# MCU.net
KiCad netlist of a schematic drawn in Altium Designer
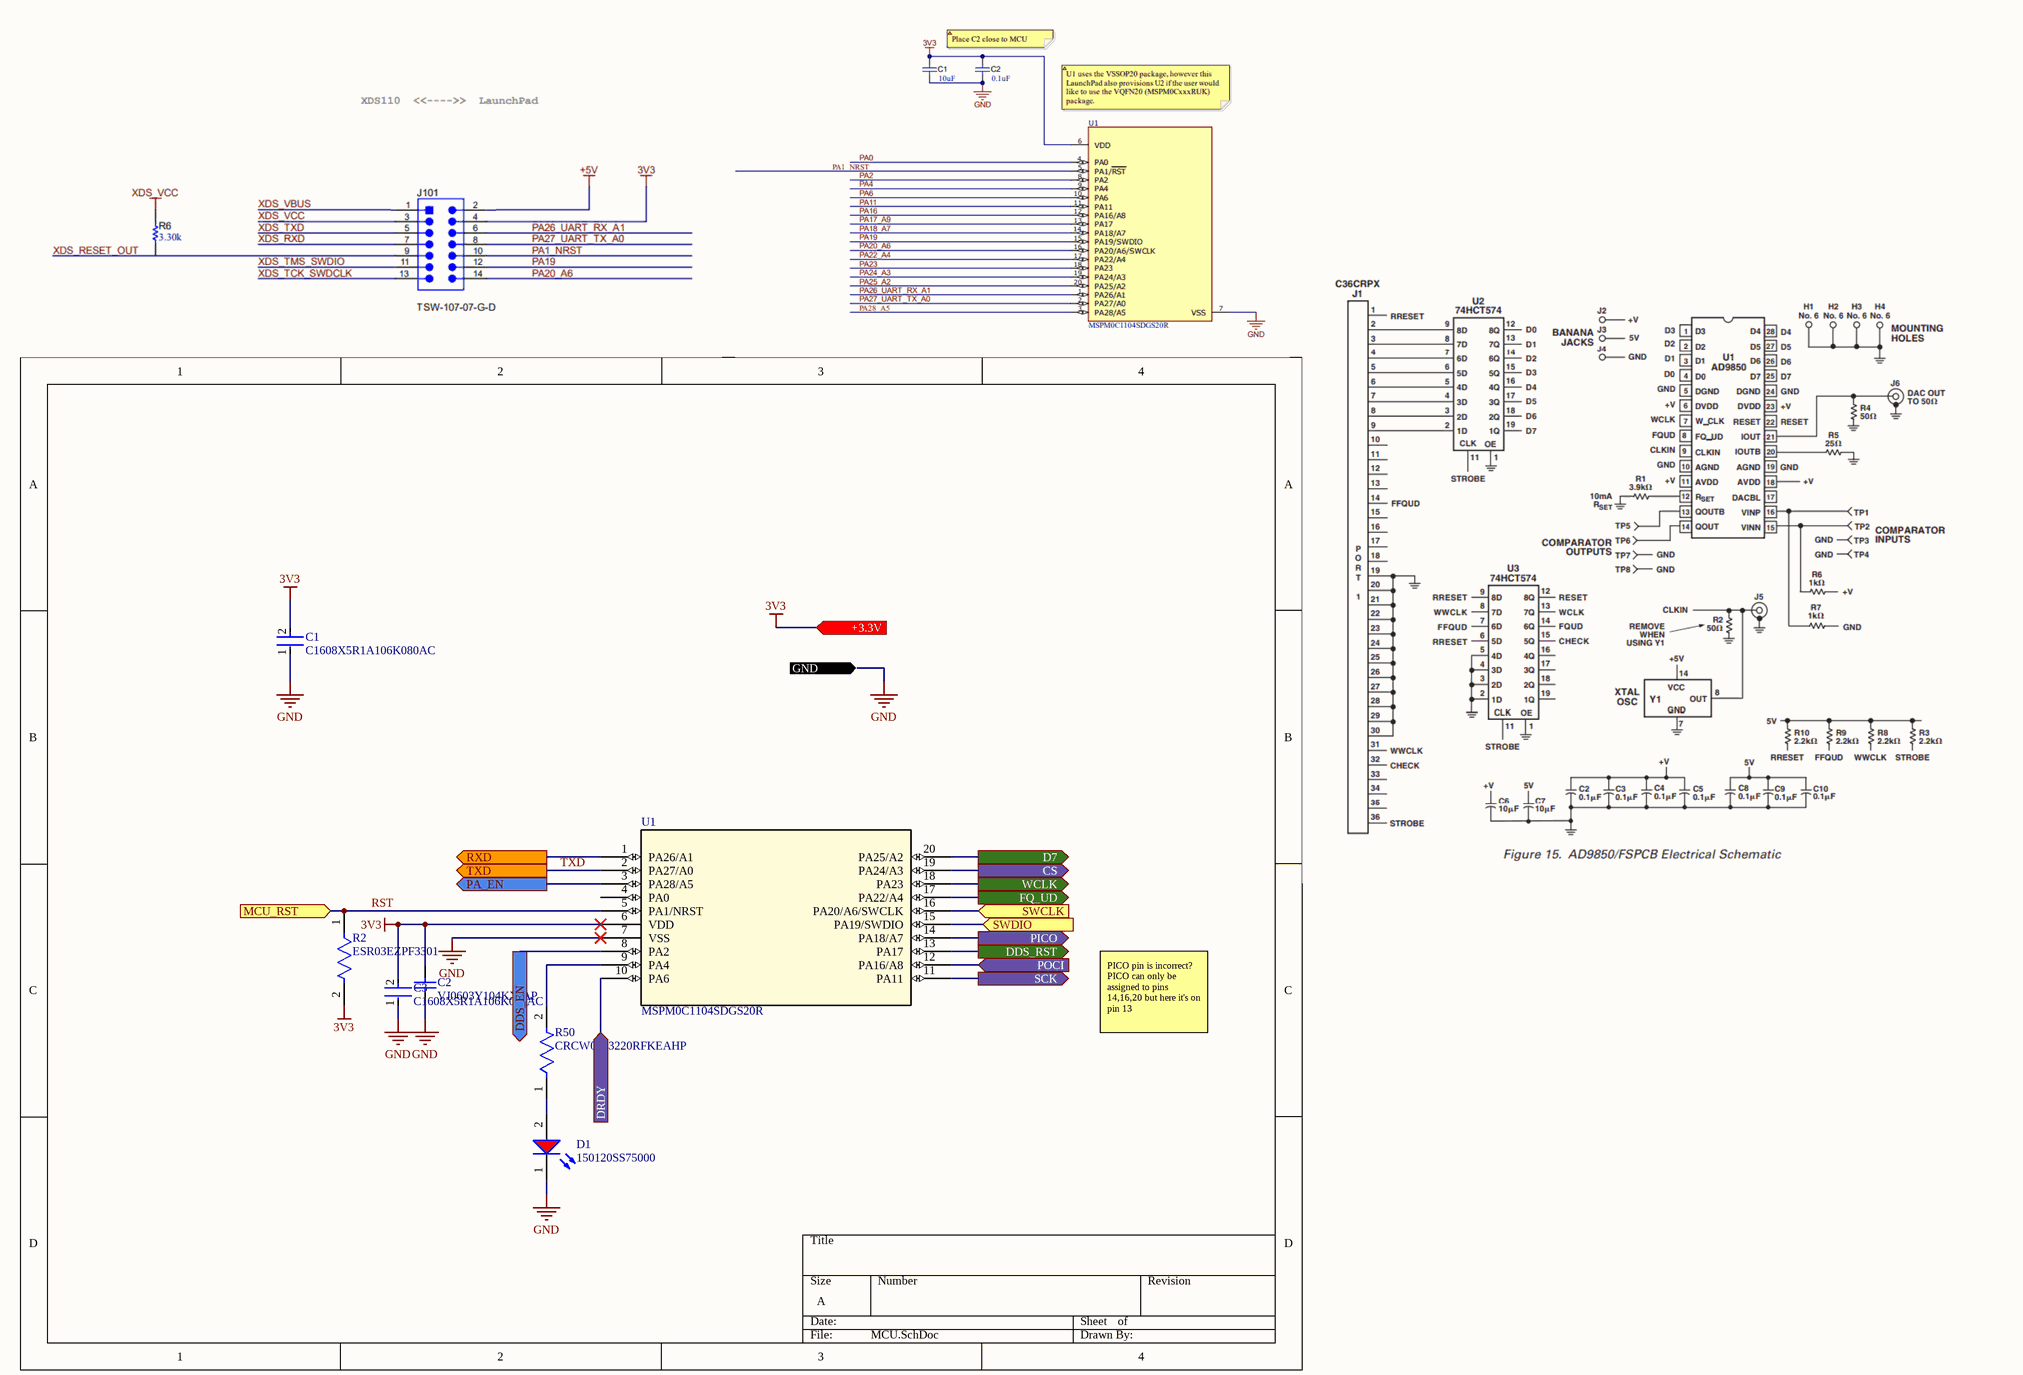
[diagram p0: MCU.SchDoc]

(export (version "E")
  (design (tool "Eeschema 10.0.6"))
  (components
    (comp (ref "C1")
      (value "C1608X5R1A106K080AC")
      (footprint "FP-C1608-080-0_1-MFG")
      (description "Multilayer Ceramic Capacitors 10μF ±10% 10V X5R SMD 0603")
      (fields (field (name "VOLTAGE") "10V") (field (name "TOLERANCE") "10%"))
      (libsource (lib "Altium Content Vault") (part "236180d848d6139a670b325ea6854c9"))
    )
    (comp (ref "C2")
      (value "VJ0603Y104KXJAP")
      (footprint "CAPC1608X92X38NL15T08")
      (fields (field (name "MANUFACTURER") "Vitramon"))
      (libsource (lib "Altium Content Vault") (part "CAP"))
    )
    (comp (ref "C3")
      (value "C1608X5R1A106K080AC")
      (footprint "FP-C1608-080-0_1-MFG")
      (description "Multilayer Ceramic Capacitors 10μF ±10% 10V X5R SMD 0603")
      (fields (field (name "VOLTAGE") "10V") (field (name "TOLERANCE") "10%"))
      (libsource (lib "Altium Content Vault") (part "236180d848d6139a670b325ea6854c9"))
    )
    (comp (ref "D1")
      (value "150120SS75000")
      (footprint "WL-SMCW_1206_150120xx75000")
      (description "Led, Red, 630 Nm, 1.9 V, 30 Ma, 60 Mcd Rohs Compliant: Yes")
      (libsource (lib "Altium Content Vault") (part "LED_Red_2A-1K"))
    )
    (comp (ref "R2")
      (value "ESR03EZPF3301")
      (footprint "FP-ESR03-IPC_A")
      (description "3.3kΩ ±1% 0.25W 0603 Anti-Surge Chip Resistor AEC-Q200")
      (fields (field (name "TOLERANCE") "1%"))
      (libsource (lib "Altium Content Vault") (part "1029c3af85768c4190bb7ad29bc67b5"))
    )
    (comp (ref "R50")
      (value "CRCW0603220RFKEAHP")
      (footprint "FP-CRCW0603-HPe3-IPC_A")
      (description "RES Thick Film, 220Ω, 1%, 0.33W, 100ppm/°C, 0603")
      (fields (field (name "TOLERANCE") "1%"))
      (libsource (lib "Altium Content Vault") (part "1029c3af85768c4190bb7ad29bc67b5"))
    )
    (comp (ref "U1")
      (value "MSPM0C1104SDGS20R")
      (footprint "DGS0020A_TEX")
      (description "24MHz ArmÂ® CortexÂ®-M0+ MCU with 16KB flash, 1KB SRAM, 12-bit ADC 20-VSSOP -40 to 125")
      (fields (field (name "COPYRIGHT") "Copyright (C) 2025 Ultra Librarian. All rights reserved."))
      (libsource (lib "MSPM0C1104SDGS20R") (part "MSPM0C1104SDGS20R"))
    )
  )
  (nets
    (net (code "1") (name "/CS") (class "Default")
      (node (ref "U1") (pin "19") (pinfunction "PA24/A3_19") (pintype "bidirectional"))
    )
    (net (code "2") (name "/D7") (class "Default")
      (node (ref "U1") (pin "20") (pinfunction "PA25/A2_20") (pintype "bidirectional"))
    )
    (net (code "3") (name "/DDS_EN") (class "Default")
      (node (ref "U1") (pin "8") (pinfunction "PA2_8") (pintype "bidirectional"))
    )
    (net (code "4") (name "/DDS_RST") (class "Default")
      (node (ref "U1") (pin "13") (pinfunction "PA17_13") (pintype "bidirectional"))
    )
    (net (code "5") (name "/DRDY") (class "Default")
      (node (ref "U1") (pin "10") (pinfunction "PA6_10") (pintype "bidirectional"))
    )
    (net (code "6") (name "/FQ_UD") (class "Default")
      (node (ref "U1") (pin "17") (pinfunction "PA22/A4_17") (pintype "bidirectional"))
    )
    (net (code "7") (name "/PA_EN") (class "Default")
      (node (ref "U1") (pin "3") (pinfunction "PA28/A5_3") (pintype "bidirectional"))
    )
    (net (code "8") (name "/PICO") (class "Default")
      (node (ref "U1") (pin "14") (pinfunction "PA18/A7_14") (pintype "bidirectional"))
    )
    (net (code "9") (name "/POCI") (class "Default")
      (node (ref "U1") (pin "12") (pinfunction "PA16/A8_12") (pintype "bidirectional"))
    )
    (net (code "10") (name "/RST") (class "Default")
      (node (ref "R2") (pin "1") (pinfunction "1_1") (pintype "passive"))
      (node (ref "U1") (pin "5") (pinfunction "PA1/NRST_5") (pintype "bidirectional"))
    )
    (net (code "11") (name "/RXD") (class "Default")
      (node (ref "U1") (pin "1") (pinfunction "PA26/A1_1") (pintype "bidirectional"))
    )
    (net (code "12") (name "/SCK") (class "Default")
      (node (ref "U1") (pin "11") (pinfunction "PA11_11") (pintype "bidirectional"))
    )
    (net (code "13") (name "/SWCLK") (class "Default")
      (node (ref "U1") (pin "16") (pinfunction "PA20/A6/SWCLK_16") (pintype "bidirectional"))
    )
    (net (code "14") (name "/SWDIO") (class "Default")
      (node (ref "U1") (pin "15") (pinfunction "PA19/SWDIO_15") (pintype "bidirectional"))
    )
    (net (code "15") (name "/TXD") (class "Default")
      (node (ref "U1") (pin "2") (pinfunction "PA27/A0_2") (pintype "bidirectional"))
    )
    (net (code "16") (name "/WCLK") (class "Default")
      (node (ref "U1") (pin "18") (pinfunction "PA23_18") (pintype "bidirectional"))
    )
    (net (code "17") (name "3V3") (class "Default")
      (node (ref "C1") (pin "2") (pinfunction "2_2") (pintype "passive"))
      (node (ref "C2") (pin "2") (pinfunction "2_2") (pintype "passive"))
      (node (ref "C3") (pin "2") (pinfunction "2_2") (pintype "passive"))
      (node (ref "R2") (pin "2") (pinfunction "2_2") (pintype "passive"))
      (node (ref "U1") (pin "6") (pinfunction "VDD_6") (pintype "power_in"))
    )
    (net (code "18") (name "GND") (class "Default")
      (node (ref "C1") (pin "1") (pinfunction "1_1") (pintype "passive"))
      (node (ref "C2") (pin "1") (pinfunction "1_1") (pintype "passive"))
      (node (ref "C3") (pin "1") (pinfunction "1_1") (pintype "passive"))
      (node (ref "D1") (pin "1") (pinfunction "K_1") (pintype "passive"))
      (node (ref "U1") (pin "7") (pinfunction "VSS_7") (pintype "power_in"))
    )
    (net (code "19") (name "Net-(D1-A)") (class "Default")
      (node (ref "D1") (pin "2") (pinfunction "A_2") (pintype "passive"))
      (node (ref "R50") (pin "1") (pinfunction "1_1") (pintype "passive"))
    )
    (net (code "20") (name "Net-(U1-PA4)") (class "Default")
      (node (ref "R50") (pin "2") (pinfunction "2_2") (pintype "passive"))
      (node (ref "U1") (pin "9") (pinfunction "PA4_9") (pintype "bidirectional"))
    )
    (net (code "21") (name "unconnected-(U1-PA0-Pad4)") (class "Default")
      (node (ref "U1") (pin "4") (pinfunction "PA0_4") (pintype "bidirectional"))
    )
  )
)
